# X-Axis_Stepper_Motor_Driver.net
KiCad netlist of a schematic drawn in Altium Designer
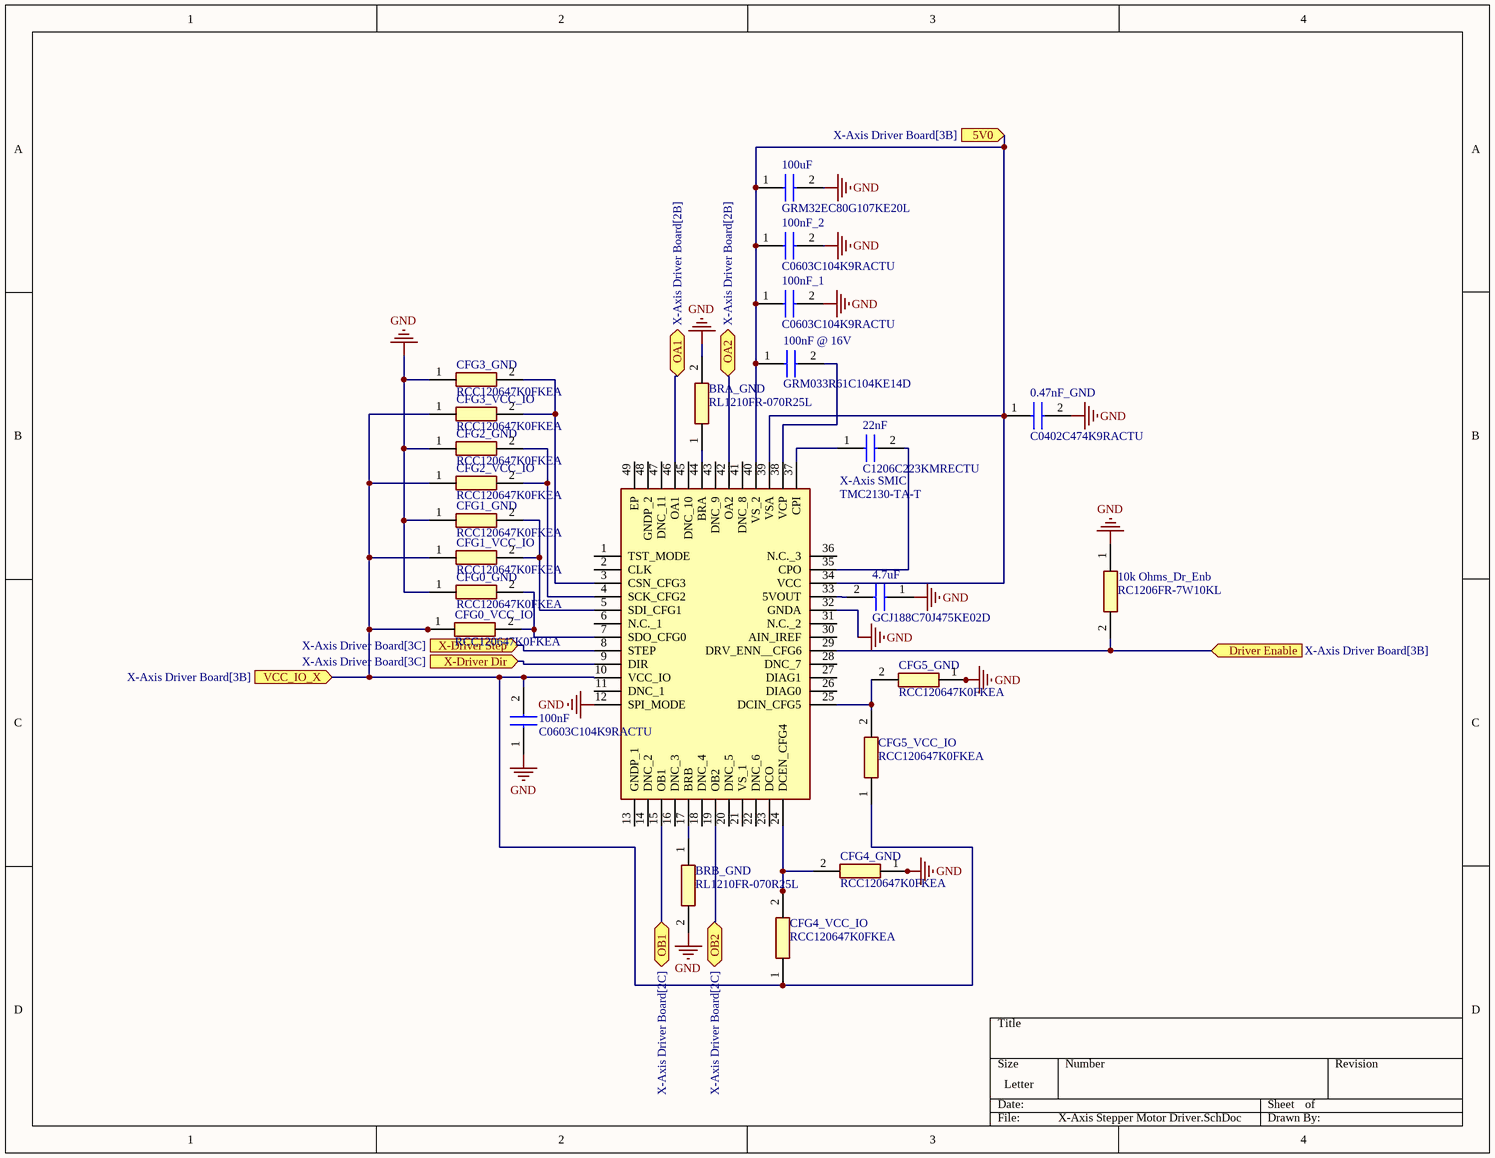
[diagram p0: X-Axis Stepper Motor Driver.SchDoc]

(export (version "E")
  (design (tool "Eeschema 10.0.6"))
  (components
    (comp (ref "0.47nF_GND")
      (value "C0402C474K9RACTU")
      (footprint "SamacSys:CAPC1005X55N")
      (description "Capacitor")
      (fields (field (name "MOUSER PART NUMBER") "80-C0402C474K9RACTU"))
      (libsource (lib "*") (part "C0402C474K9RACTU"))
    )
    (comp (ref "4.7uF")
      (value "GCJ188C70J475KE02D")
      (footprint "SamacSys:CAPC1608X100N")
      (description "Capacitor")
      (fields (field (name "MOUSER PART NUMBER") "81-GCJ188C70J475KE2D"))
      (libsource (lib "*") (part "GCJ188C70J475KE02D"))
    )
    (comp (ref "10k Ohms_Dr_Enb")
      (value "RC1206FR-7W10KL")
      (footprint "SamacSys:RESC3116X65N")
      (description "Resistor")
      (libsource (lib "*") (part "RC1206FR-7W10KL"))
    )
    (comp (ref "22nF")
      (value "C1206C223KMRECTU")
      (footprint "SamacSys:C1206")
      (description "Capacitor")
      (fields (field (name "MOUSER PART NUMBER") "80-C1206C223KMRECTU"))
      (libsource (lib "*") (part "C1206C223KMRECTU"))
    )
    (comp (ref "100nF")
      (value "C0603C104K9RACTU")
      (footprint "SamacSys:C0603")
      (description "Capacitor")
      (fields (field (name "MOUSER PART NUMBER") "80-C0603C104K9R"))
      (libsource (lib "*") (part "C0603C104K9RACTU"))
    )
    (comp (ref "100nF @ 16V")
      (value "GRM033R61C104KE14D")
      (footprint "SamacSys:CAPC0603X33N")
      (description "Capacitor")
      (fields (field (name "MOUSER PART NUMBER") "81-GRM033R61C104KE4D"))
      (libsource (lib "*") (part "GRM033R61C104KE14D"))
    )
    (comp (ref "100nF_1")
      (value "C0603C104K9RACTU")
      (footprint "SamacSys:C0603")
      (description "Capacitor")
      (fields (field (name "MOUSER PART NUMBER") "80-C0603C104K9R"))
      (libsource (lib "*") (part "C0603C104K9RACTU"))
    )
    (comp (ref "100nF_2")
      (value "C0603C104K9RACTU")
      (footprint "SamacSys:C0603")
      (description "Capacitor")
      (fields (field (name "MOUSER PART NUMBER") "80-C0603C104K9R"))
      (libsource (lib "*") (part "C0603C104K9RACTU"))
    )
    (comp (ref "100uF")
      (value "GRM32EC80G107KE20L")
      (footprint "SamacSys:CAPC3225X270N")
      (description "Capacitor")
      (fields (field (name "MOUSER PART NUMBER") "81-GRM32EC80G107KE0L"))
      (libsource (lib "*") (part "GRM32EC80G107KE20L"))
    )
    (comp (ref "BRA_GND")
      (value "RL1210FR-070R25L")
      (footprint "SamacSys:RESC3126X65N")
      (description "Resistor")
      (fields (field (name "MOUSER PART NUMBER") "603-RL1210FR-070R25L"))
      (libsource (lib "") (part "RL1210FR-070R25L_1"))
    )
    (comp (ref "BRB_GND")
      (value "RL1210FR-070R25L")
      (footprint "SamacSys:RESC3126X65N")
      (description "Resistor")
      (fields (field (name "MOUSER PART NUMBER") "603-RL1210FR-070R25L"))
      (libsource (lib "*") (part "RL1210FR-070R25L"))
    )
    (comp (ref "CFG0_GND")
      (value "RCC120647K0FKEA")
      (footprint "SamacSys:RCC1206_e3")
      (description "Resistor")
      (fields (field (name "MOUSER PART NUMBER") "71-RCC120647K0FKEA"))
      (libsource (lib "") (part "RCC120647K0FKEA_1"))
    )
    (comp (ref "CFG0_VCC_IO")
      (value "RCC120647K0FKEA")
      (footprint "SamacSys:RCC1206_e3")
      (description "Resistor")
      (fields (field (name "MOUSER PART NUMBER") "71-RCC120647K0FKEA"))
      (libsource (lib "") (part "RCC120647K0FKEA_1"))
    )
    (comp (ref "CFG1_GND")
      (value "RCC120647K0FKEA")
      (footprint "SamacSys:RCC1206_e3")
      (description "Resistor")
      (fields (field (name "MOUSER PART NUMBER") "71-RCC120647K0FKEA"))
      (libsource (lib "") (part "RCC120647K0FKEA_1"))
    )
    (comp (ref "CFG1_VCC_IO")
      (value "RCC120647K0FKEA")
      (footprint "SamacSys:RCC1206_e3")
      (description "Resistor")
      (fields (field (name "MOUSER PART NUMBER") "71-RCC120647K0FKEA"))
      (libsource (lib "") (part "RCC120647K0FKEA_1"))
    )
    (comp (ref "CFG2_GND")
      (value "RCC120647K0FKEA")
      (footprint "SamacSys:RCC1206_e3")
      (description "Resistor")
      (fields (field (name "MOUSER PART NUMBER") "71-RCC120647K0FKEA"))
      (libsource (lib "") (part "RCC120647K0FKEA_1"))
    )
    (comp (ref "CFG2_VCC_IO")
      (value "RCC120647K0FKEA")
      (footprint "SamacSys:RCC1206_e3")
      (description "Resistor")
      (fields (field (name "MOUSER PART NUMBER") "71-RCC120647K0FKEA"))
      (libsource (lib "") (part "RCC120647K0FKEA_1"))
    )
    (comp (ref "CFG3_GND")
      (value "RCC120647K0FKEA")
      (footprint "SamacSys:RCC1206_e3")
      (description "Resistor")
      (fields (field (name "MOUSER PART NUMBER") "71-RCC120647K0FKEA"))
      (libsource (lib "") (part "RCC120647K0FKEA_1"))
    )
    (comp (ref "CFG3_VCC_IO")
      (value "RCC120647K0FKEA")
      (footprint "SamacSys:RCC1206_e3")
      (description "Resistor")
      (fields (field (name "MOUSER PART NUMBER") "71-RCC120647K0FKEA"))
      (libsource (lib "") (part "RCC120647K0FKEA_1"))
    )
    (comp (ref "CFG4_GND")
      (value "RCC120647K0FKEA")
      (footprint "SamacSys:RCC1206_e3")
      (description "Resistor")
      (fields (field (name "MOUSER PART NUMBER") "71-RCC120647K0FKEA"))
      (libsource (lib "") (part "RCC120647K0FKEA_2"))
    )
    (comp (ref "CFG4_VCC_IO")
      (value "RCC120647K0FKEA")
      (footprint "SamacSys:RCC1206_e3")
      (description "Resistor")
      (fields (field (name "MOUSER PART NUMBER") "71-RCC120647K0FKEA"))
      (libsource (lib "*") (part "RCC120647K0FKEA"))
    )
    (comp (ref "CFG5_GND")
      (value "RCC120647K0FKEA")
      (footprint "SamacSys:RCC1206_e3")
      (description "Resistor")
      (fields (field (name "MOUSER PART NUMBER") "71-RCC120647K0FKEA"))
      (libsource (lib "") (part "RCC120647K0FKEA_2"))
    )
    (comp (ref "CFG5_VCC_IO")
      (value "RCC120647K0FKEA")
      (footprint "SamacSys:RCC1206_e3")
      (description "Resistor")
      (fields (field (name "MOUSER PART NUMBER") "71-RCC120647K0FKEA"))
      (libsource (lib "*") (part "RCC120647K0FKEA"))
    )
    (comp (ref "X-Axis SMIC")
      (value "TMC2130-TA-T")
      (footprint "SamacSys:QFP50P900X900X120-49N")
      (description "Integrated Circuit")
      (fields (field (name "MOUSER PART NUMBER") "700-TMC2130-TA-T"))
      (libsource (lib "*") (part "TMC2130-TA-T"))
    )
  )
  (nets
    (net (code "1") (name "/5V0") (class "Default")
      (node (ref "0.47nF_GND") (pin "1") (pinfunction "1_1") (pintype "passive"))
      (node (ref "100nF @ 16V") (pin "1") (pinfunction "1_1") (pintype "passive"))
      (node (ref "100nF_1") (pin "1") (pinfunction "1_1") (pintype "passive"))
      (node (ref "100nF_2") (pin "1") (pinfunction "1_1") (pintype "passive"))
      (node (ref "100uF") (pin "1") (pinfunction "1_1") (pintype "passive"))
      (node (ref "X-Axis SMIC") (pin "34") (pinfunction "VCC_34") (pintype "passive"))
      (node (ref "X-Axis SMIC") (pin "39") (pinfunction "VSA_39") (pintype "passive"))
      (node (ref "X-Axis SMIC") (pin "40") (pinfunction "VS_2_40") (pintype "passive"))
    )
    (net (code "2") (name "/Driver Enable") (class "Default")
      (node (ref "10k Ohms_Dr_Enb") (pin "2") (pinfunction "2_2") (pintype "passive"))
      (node (ref "X-Axis SMIC") (pin "29") (pinfunction "DRV_ENN__CFG6_29") (pintype "passive"))
    )
    (net (code "3") (name "/OA1") (class "Default")
      (node (ref "X-Axis SMIC") (pin "46") (pinfunction "OA1_46") (pintype "passive"))
    )
    (net (code "4") (name "/OA2") (class "Default")
      (node (ref "X-Axis SMIC") (pin "42") (pinfunction "OA2_42") (pintype "passive"))
    )
    (net (code "5") (name "/OB1") (class "Default")
      (node (ref "X-Axis SMIC") (pin "15") (pinfunction "OB1_15") (pintype "passive"))
    )
    (net (code "6") (name "/OB2") (class "Default")
      (node (ref "X-Axis SMIC") (pin "19") (pinfunction "OB2_19") (pintype "passive"))
    )
    (net (code "7") (name "/VCC_IO_X") (class "Default")
      (node (ref "100nF") (pin "2") (pinfunction "2_2") (pintype "passive"))
      (node (ref "CFG0_VCC_IO") (pin "1") (pinfunction "1_1") (pintype "passive"))
      (node (ref "CFG1_VCC_IO") (pin "1") (pinfunction "1_1") (pintype "passive"))
      (node (ref "CFG2_VCC_IO") (pin "1") (pinfunction "1_1") (pintype "passive"))
      (node (ref "CFG3_VCC_IO") (pin "1") (pinfunction "1_1") (pintype "passive"))
      (node (ref "CFG4_VCC_IO") (pin "1") (pinfunction "1_1") (pintype "passive"))
      (node (ref "CFG5_VCC_IO") (pin "1") (pinfunction "1_1") (pintype "passive"))
      (node (ref "X-Axis SMIC") (pin "10") (pinfunction "VCC_IO_10") (pintype "passive"))
    )
    (net (code "8") (name "/X-Driver Dir") (class "Default")
      (node (ref "X-Axis SMIC") (pin "9") (pinfunction "DIR_9") (pintype "passive"))
    )
    (net (code "9") (name "/X-Driver Step") (class "Default")
      (node (ref "X-Axis SMIC") (pin "8") (pinfunction "STEP_8") (pintype "passive"))
    )
    (net (code "10") (name "GND") (class "Default")
      (node (ref "0.47nF_GND") (pin "2") (pinfunction "2_2") (pintype "passive"))
      (node (ref "100nF") (pin "1") (pinfunction "1_1") (pintype "passive"))
      (node (ref "100nF_1") (pin "2") (pinfunction "2_2") (pintype "passive"))
      (node (ref "100nF_2") (pin "2") (pinfunction "2_2") (pintype "passive"))
      (node (ref "100uF") (pin "2") (pinfunction "2_2") (pintype "passive"))
      (node (ref "10k Ohms_Dr_Enb") (pin "1") (pinfunction "1_1") (pintype "passive"))
      (node (ref "4.7uF") (pin "1") (pinfunction "1_1") (pintype "passive"))
      (node (ref "BRA_GND") (pin "2") (pinfunction "2_2") (pintype "passive"))
      (node (ref "BRB_GND") (pin "2") (pinfunction "2_2") (pintype "passive"))
      (node (ref "CFG0_GND") (pin "1") (pinfunction "1_1") (pintype "passive"))
      (node (ref "CFG1_GND") (pin "1") (pinfunction "1_1") (pintype "passive"))
      (node (ref "CFG2_GND") (pin "1") (pinfunction "1_1") (pintype "passive"))
      (node (ref "CFG3_GND") (pin "1") (pinfunction "1_1") (pintype "passive"))
      (node (ref "CFG4_GND") (pin "1") (pinfunction "1_1") (pintype "passive"))
      (node (ref "CFG5_GND") (pin "1") (pinfunction "1_1") (pintype "passive"))
      (node (ref "X-Axis SMIC") (pin "12") (pinfunction "SPI_MODE_12") (pintype "passive"))
      (node (ref "X-Axis SMIC") (pin "32") (pinfunction "GNDA_32") (pintype "passive"))
    )
    (net (code "11") (name "Net-(X-Axis SMIC-5VOUT)") (class "Default")
      (node (ref "4.7uF") (pin "2") (pinfunction "2_2") (pintype "passive"))
      (node (ref "X-Axis SMIC") (pin "33") (pinfunction "5VOUT_33") (pintype "passive"))
    )
    (net (code "12") (name "Net-(X-Axis SMIC-BRA)") (class "Default")
      (node (ref "BRA_GND") (pin "1") (pinfunction "1_1") (pintype "passive"))
      (node (ref "X-Axis SMIC") (pin "44") (pinfunction "BRA_44") (pintype "passive"))
    )
    (net (code "13") (name "Net-(X-Axis SMIC-BRB)") (class "Default")
      (node (ref "BRB_GND") (pin "1") (pinfunction "1_1") (pintype "passive"))
      (node (ref "X-Axis SMIC") (pin "17") (pinfunction "BRB_17") (pintype "passive"))
    )
    (net (code "14") (name "Net-(X-Axis SMIC-CPI)") (class "Default")
      (node (ref "22nF") (pin "1") (pinfunction "1_1") (pintype "passive"))
      (node (ref "X-Axis SMIC") (pin "37") (pinfunction "CPI_37") (pintype "passive"))
    )
    (net (code "15") (name "Net-(X-Axis SMIC-CPO)") (class "Default")
      (node (ref "22nF") (pin "2") (pinfunction "2_2") (pintype "passive"))
      (node (ref "X-Axis SMIC") (pin "35") (pinfunction "CPO_35") (pintype "passive"))
    )
    (net (code "16") (name "Net-(X-Axis SMIC-CSN_CFG3)") (class "Default")
      (node (ref "CFG3_GND") (pin "2") (pinfunction "2_2") (pintype "passive"))
      (node (ref "CFG3_VCC_IO") (pin "2") (pinfunction "2_2") (pintype "passive"))
      (node (ref "X-Axis SMIC") (pin "3") (pinfunction "CSN_CFG3_3") (pintype "passive"))
    )
    (net (code "17") (name "Net-(X-Axis SMIC-DCEN_CFG4)") (class "Default")
      (node (ref "CFG4_GND") (pin "2") (pinfunction "2_2") (pintype "passive"))
      (node (ref "CFG4_VCC_IO") (pin "2") (pinfunction "2_2") (pintype "passive"))
      (node (ref "X-Axis SMIC") (pin "24") (pinfunction "DCEN_CFG4_24") (pintype "passive"))
    )
    (net (code "18") (name "Net-(X-Axis SMIC-DCIN_CFG5)") (class "Default")
      (node (ref "CFG5_GND") (pin "2") (pinfunction "2_2") (pintype "passive"))
      (node (ref "CFG5_VCC_IO") (pin "2") (pinfunction "2_2") (pintype "passive"))
      (node (ref "X-Axis SMIC") (pin "25") (pinfunction "DCIN_CFG5_25") (pintype "passive"))
    )
    (net (code "19") (name "Net-(X-Axis SMIC-SCK_CFG2)") (class "Default")
      (node (ref "CFG2_GND") (pin "2") (pinfunction "2_2") (pintype "passive"))
      (node (ref "CFG2_VCC_IO") (pin "2") (pinfunction "2_2") (pintype "passive"))
      (node (ref "X-Axis SMIC") (pin "4") (pinfunction "SCK_CFG2_4") (pintype "passive"))
    )
    (net (code "20") (name "Net-(X-Axis SMIC-SDI_CFG1)") (class "Default")
      (node (ref "CFG1_GND") (pin "2") (pinfunction "2_2") (pintype "passive"))
      (node (ref "CFG1_VCC_IO") (pin "2") (pinfunction "2_2") (pintype "passive"))
      (node (ref "X-Axis SMIC") (pin "5") (pinfunction "SDI_CFG1_5") (pintype "passive"))
    )
    (net (code "21") (name "Net-(X-Axis SMIC-SDO_CFG0)") (class "Default")
      (node (ref "CFG0_GND") (pin "2") (pinfunction "2_2") (pintype "passive"))
      (node (ref "CFG0_VCC_IO") (pin "2") (pinfunction "2_2") (pintype "passive"))
      (node (ref "X-Axis SMIC") (pin "7") (pinfunction "SDO_CFG0_7") (pintype "passive"))
    )
    (net (code "22") (name "Net-(X-Axis SMIC-VCP)") (class "Default")
      (node (ref "100nF @ 16V") (pin "2") (pinfunction "2_2") (pintype "passive"))
      (node (ref "X-Axis SMIC") (pin "38") (pinfunction "VCP_38") (pintype "passive"))
    )
    (net (code "23") (name "unconnected-(X-Axis SMIC-AIN_IREF-Pad30)") (class "Default")
      (node (ref "X-Axis SMIC") (pin "30") (pinfunction "AIN_IREF_30") (pintype "passive"))
    )
    (net (code "24") (name "unconnected-(X-Axis SMIC-CLK-Pad2)") (class "Default")
      (node (ref "X-Axis SMIC") (pin "2") (pinfunction "CLK_2") (pintype "passive"))
    )
    (net (code "25") (name "unconnected-(X-Axis SMIC-DCO-Pad23)") (class "Default")
      (node (ref "X-Axis SMIC") (pin "23") (pinfunction "DCO_23") (pintype "passive"))
    )
    (net (code "26") (name "unconnected-(X-Axis SMIC-DIAG0-Pad26)") (class "Default")
      (node (ref "X-Axis SMIC") (pin "26") (pinfunction "DIAG0_26") (pintype "passive"))
    )
    (net (code "27") (name "unconnected-(X-Axis SMIC-DIAG1-Pad27)") (class "Default")
      (node (ref "X-Axis SMIC") (pin "27") (pinfunction "DIAG1_27") (pintype "passive"))
    )
    (net (code "28") (name "unconnected-(X-Axis SMIC-DNC_1-Pad11)") (class "Default")
      (node (ref "X-Axis SMIC") (pin "11") (pinfunction "DNC_1_11") (pintype "passive"))
    )
    (net (code "29") (name "unconnected-(X-Axis SMIC-DNC_2-Pad14)") (class "Default")
      (node (ref "X-Axis SMIC") (pin "14") (pinfunction "DNC_2_14") (pintype "passive"))
    )
    (net (code "30") (name "unconnected-(X-Axis SMIC-DNC_3-Pad16)") (class "Default")
      (node (ref "X-Axis SMIC") (pin "16") (pinfunction "DNC_3_16") (pintype "passive"))
    )
    (net (code "31") (name "unconnected-(X-Axis SMIC-DNC_4-Pad18)") (class "Default")
      (node (ref "X-Axis SMIC") (pin "18") (pinfunction "DNC_4_18") (pintype "passive"))
    )
    (net (code "32") (name "unconnected-(X-Axis SMIC-DNC_5-Pad20)") (class "Default")
      (node (ref "X-Axis SMIC") (pin "20") (pinfunction "DNC_5_20") (pintype "passive"))
    )
    (net (code "33") (name "unconnected-(X-Axis SMIC-DNC_6-Pad22)") (class "Default")
      (node (ref "X-Axis SMIC") (pin "22") (pinfunction "DNC_6_22") (pintype "passive"))
    )
    (net (code "34") (name "unconnected-(X-Axis SMIC-DNC_7-Pad28)") (class "Default")
      (node (ref "X-Axis SMIC") (pin "28") (pinfunction "DNC_7_28") (pintype "passive"))
    )
    (net (code "35") (name "unconnected-(X-Axis SMIC-DNC_8-Pad41)") (class "Default")
      (node (ref "X-Axis SMIC") (pin "41") (pinfunction "DNC_8_41") (pintype "passive"))
    )
    (net (code "36") (name "unconnected-(X-Axis SMIC-DNC_9-Pad43)") (class "Default")
      (node (ref "X-Axis SMIC") (pin "43") (pinfunction "DNC_9_43") (pintype "passive"))
    )
    (net (code "37") (name "unconnected-(X-Axis SMIC-DNC_10-Pad45)") (class "Default")
      (node (ref "X-Axis SMIC") (pin "45") (pinfunction "DNC_10_45") (pintype "passive"))
    )
    (net (code "38") (name "unconnected-(X-Axis SMIC-DNC_11-Pad47)") (class "Default")
      (node (ref "X-Axis SMIC") (pin "47") (pinfunction "DNC_11_47") (pintype "passive"))
    )
    (net (code "39") (name "unconnected-(X-Axis SMIC-EP-Pad49)") (class "Default")
      (node (ref "X-Axis SMIC") (pin "49") (pinfunction "EP_49") (pintype "passive"))
    )
    (net (code "40") (name "unconnected-(X-Axis SMIC-GNDP_1-Pad13)") (class "Default")
      (node (ref "X-Axis SMIC") (pin "13") (pinfunction "GNDP_1_13") (pintype "passive"))
    )
    (net (code "41") (name "unconnected-(X-Axis SMIC-GNDP_2-Pad48)") (class "Default")
      (node (ref "X-Axis SMIC") (pin "48") (pinfunction "GNDP_2_48") (pintype "passive"))
    )
    (net (code "42") (name "unconnected-(X-Axis SMIC-N.C._1-Pad6)") (class "Default")
      (node (ref "X-Axis SMIC") (pin "6") (pinfunction "N.C._1_6") (pintype "passive"))
    )
    (net (code "43") (name "unconnected-(X-Axis SMIC-N.C._2-Pad31)") (class "Default")
      (node (ref "X-Axis SMIC") (pin "31") (pinfunction "N.C._2_31") (pintype "passive"))
    )
    (net (code "44") (name "unconnected-(X-Axis SMIC-N.C._3-Pad36)") (class "Default")
      (node (ref "X-Axis SMIC") (pin "36") (pinfunction "N.C._3_36") (pintype "passive"))
    )
    (net (code "45") (name "unconnected-(X-Axis SMIC-TST_MODE-Pad1)") (class "Default")
      (node (ref "X-Axis SMIC") (pin "1") (pinfunction "TST_MODE_1") (pintype "passive"))
    )
    (net (code "46") (name "unconnected-(X-Axis SMIC-VS_1-Pad21)") (class "Default")
      (node (ref "X-Axis SMIC") (pin "21") (pinfunction "VS_1_21") (pintype "passive"))
    )
  )
)
